# 05_LOWPASS_IQ.net
KiCad netlist of a schematic drawn in Altium Designer
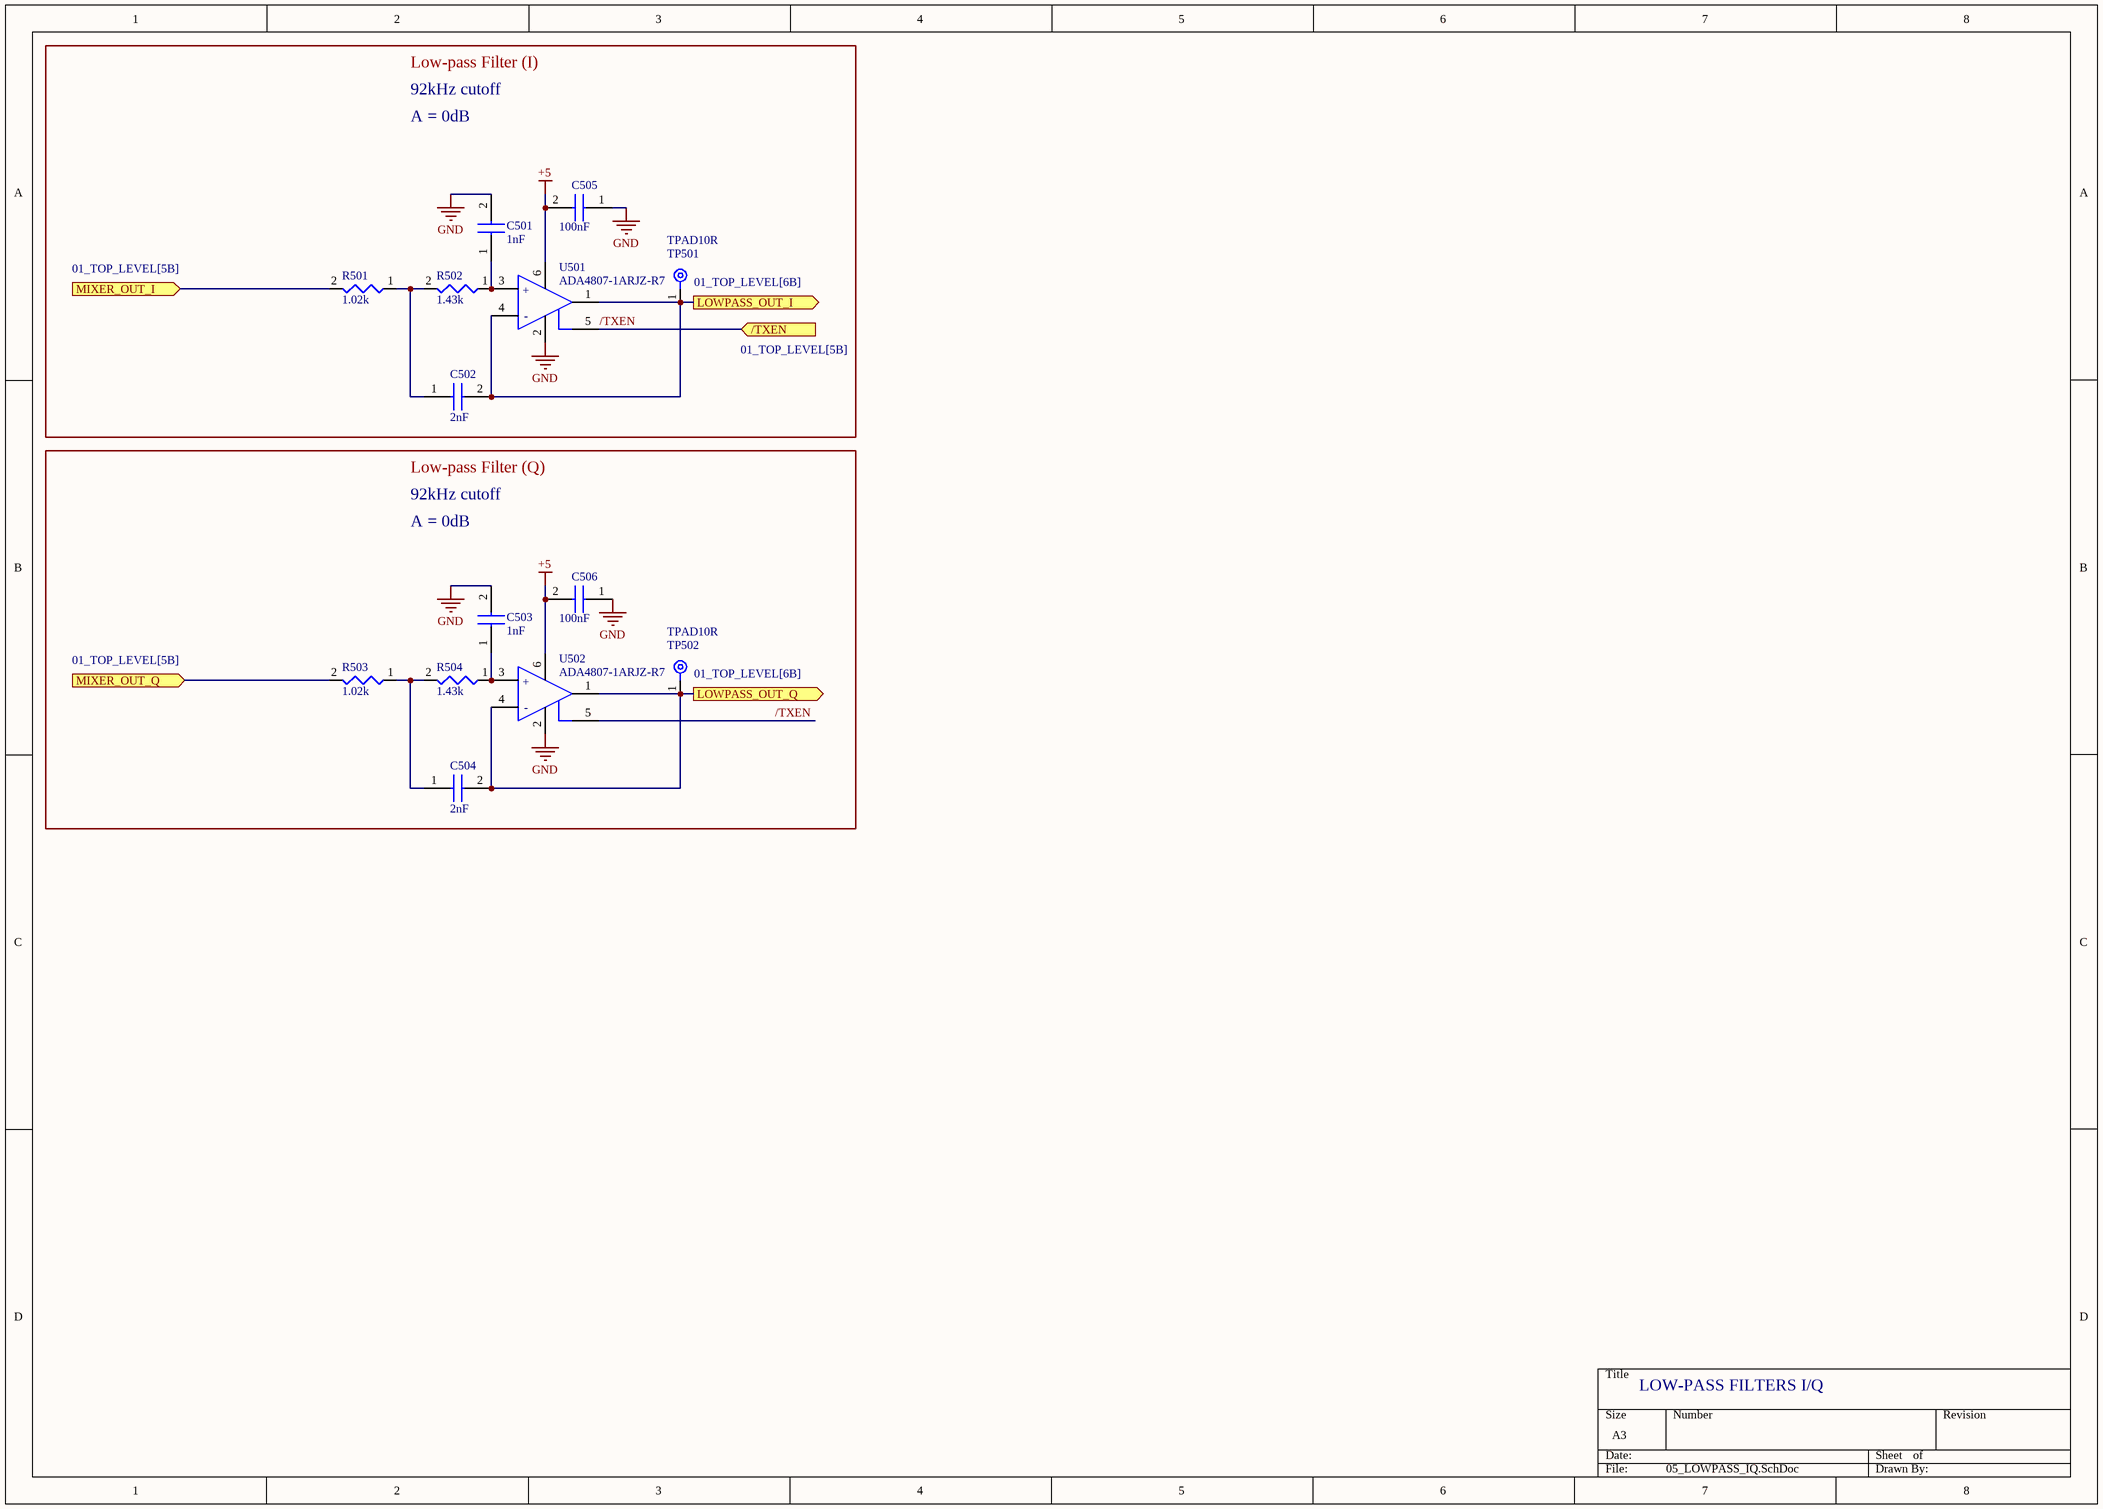
[diagram p0: 05_LOWPASS_IQ.SchDoc]

(export (version "E")
  (design (tool "Eeschema 10.0.6"))
  (components
    (comp (ref "C501")
      (value "1nF")
      (footprint "CAP_0805")
      (description "Capacitor SMD 0805")
      (libsource (lib "Passive_Components") (part "CAP_0805"))
    )
    (comp (ref "C502")
      (value "2nF")
      (footprint "CAP_0805")
      (description "Capacitor SMD 0805")
      (libsource (lib "Passive_Components") (part "CAP_0805"))
    )
    (comp (ref "C503")
      (value "1nF")
      (footprint "CAP_0805")
      (description "Capacitor SMD 0805")
      (libsource (lib "Passive_Components") (part "CAP_0805"))
    )
    (comp (ref "C504")
      (value "2nF")
      (footprint "CAP_0805")
      (description "Capacitor SMD 0805")
      (libsource (lib "Passive_Components") (part "CAP_0805"))
    )
    (comp (ref "C505")
      (value "100nF")
      (footprint "CAP_0805")
      (description "Capacitor SMD 0805")
      (libsource (lib "Passive_Components") (part "CAP_0805"))
    )
    (comp (ref "C506")
      (value "100nF")
      (footprint "CAP_0805")
      (description "Capacitor SMD 0805")
      (libsource (lib "Passive_Components") (part "CAP_0805"))
    )
    (comp (ref "R501")
      (value "1.02k")
      (footprint "RES_0805")
      (description "Resistor SMD 0805")
      (libsource (lib "Passive_Components") (part "RES_0805"))
    )
    (comp (ref "R502")
      (value "1.43k")
      (footprint "RES_0805")
      (description "Resistor SMD 0805")
      (libsource (lib "Passive_Components") (part "RES_0805"))
    )
    (comp (ref "R503")
      (value "1.02k")
      (footprint "RES_0805")
      (description "Resistor SMD 0805")
      (libsource (lib "Passive_Components") (part "RES_0805"))
    )
    (comp (ref "R504")
      (value "1.43k")
      (footprint "RES_0805")
      (description "Resistor SMD 0805")
      (libsource (lib "Passive_Components") (part "RES_0805"))
    )
    (comp (ref "TP501")
      (value "TPAD10R")
      (footprint "TEST_POINT")
      (description "Testpont Pad 10R")
      (libsource (lib "PASSIVE_COMPONENTS") (part "TEST_POINT"))
    )
    (comp (ref "TP502")
      (value "TPAD10R")
      (footprint "TEST_POINT")
      (description "Testpont Pad 10R")
      (libsource (lib "PASSIVE_COMPONENTS") (part "TEST_POINT"))
    )
    (comp (ref "U501")
      (value "ADA4807-1ARJZ-R7")
      (footprint "FP-RJ-6-IPC_A")
      (description "IC OPAMP VFB 1 CIRCUIT SOT23-6")
      (libsource (lib "Altium Content Vault") (part "0cc169e61f44c0172c2773b4ba3b2c6"))
    )
    (comp (ref "U502")
      (value "ADA4807-1ARJZ-R7")
      (footprint "FP-RJ-6-IPC_A")
      (description "IC OPAMP VFB 1 CIRCUIT SOT23-6")
      (libsource (lib "Altium Content Vault") (part "0cc169e61f44c0172c2773b4ba3b2c6"))
    )
  )
  (nets
    (net (code "1") (name "+5") (class "Default")
      (node (ref "C505") (pin "2") (pinfunction "2_2") (pintype "passive"))
      (node (ref "C506") (pin "2") (pinfunction "2_2") (pintype "passive"))
      (node (ref "U501") (pin "6") (pinfunction "+VS_6") (pintype "power_in"))
      (node (ref "U502") (pin "6") (pinfunction "+VS_6") (pintype "power_in"))
    )
    (net (code "2") (name "/LOWPASS_OUT_I") (class "Default")
      (node (ref "C502") (pin "2") (pinfunction "2_2") (pintype "passive"))
      (node (ref "TP501") (pin "1") (pinfunction "1_1") (pintype "passive"))
      (node (ref "U501") (pin "1") (pinfunction "VOUT_1") (pintype "passive"))
      (node (ref "U501") (pin "4") (pinfunction "-IN_4") (pintype "tri_state"))
    )
    (net (code "3") (name "/LOWPASS_OUT_Q") (class "Default")
      (node (ref "C504") (pin "2") (pinfunction "2_2") (pintype "passive"))
      (node (ref "TP502") (pin "1") (pinfunction "1_1") (pintype "passive"))
      (node (ref "U502") (pin "1") (pinfunction "VOUT_1") (pintype "passive"))
      (node (ref "U502") (pin "4") (pinfunction "-IN_4") (pintype "tri_state"))
    )
    (net (code "4") (name "/MIXER_OUT_I") (class "Default")
      (node (ref "R501") (pin "2") (pinfunction "2_2") (pintype "passive"))
    )
    (net (code "5") (name "/MIXER_OUT_Q") (class "Default")
      (node (ref "R503") (pin "2") (pinfunction "2_2") (pintype "passive"))
    )
    (net (code "6") (name "/{slash}TXEN") (class "Default")
      (node (ref "U501") (pin "5") (pinfunction "~{DISABLE}_5") (pintype "passive"))
      (node (ref "U502") (pin "5") (pinfunction "~{DISABLE}_5") (pintype "passive"))
    )
    (net (code "7") (name "GND") (class "Default")
      (node (ref "C501") (pin "2") (pinfunction "2_2") (pintype "passive"))
      (node (ref "C503") (pin "2") (pinfunction "2_2") (pintype "passive"))
      (node (ref "C505") (pin "1") (pinfunction "1_1") (pintype "passive"))
      (node (ref "C506") (pin "1") (pinfunction "1_1") (pintype "passive"))
      (node (ref "U501") (pin "2") (pinfunction "-VS_2") (pintype "power_in"))
      (node (ref "U502") (pin "2") (pinfunction "-VS_2") (pintype "power_in"))
    )
    (net (code "8") (name "Net-(C502-Pad1)") (class "Default")
      (node (ref "C502") (pin "1") (pinfunction "1_1") (pintype "passive"))
      (node (ref "R501") (pin "1") (pinfunction "1_1") (pintype "passive"))
      (node (ref "R502") (pin "2") (pinfunction "2_2") (pintype "passive"))
    )
    (net (code "9") (name "Net-(C504-Pad1)") (class "Default")
      (node (ref "C504") (pin "1") (pinfunction "1_1") (pintype "passive"))
      (node (ref "R503") (pin "1") (pinfunction "1_1") (pintype "passive"))
      (node (ref "R504") (pin "2") (pinfunction "2_2") (pintype "passive"))
    )
    (net (code "10") (name "Net-(U501-+IN)") (class "Default")
      (node (ref "C501") (pin "1") (pinfunction "1_1") (pintype "passive"))
      (node (ref "R502") (pin "1") (pinfunction "1_1") (pintype "passive"))
      (node (ref "U501") (pin "3") (pinfunction "+IN_3") (pintype "tri_state"))
    )
    (net (code "11") (name "Net-(U502-+IN)") (class "Default")
      (node (ref "C503") (pin "1") (pinfunction "1_1") (pintype "passive"))
      (node (ref "R504") (pin "1") (pinfunction "1_1") (pintype "passive"))
      (node (ref "U502") (pin "3") (pinfunction "+IN_3") (pintype "tri_state"))
    )
  )
)
